# StartupMCU.net
KiCad netlist of a schematic drawn in Altium Designer
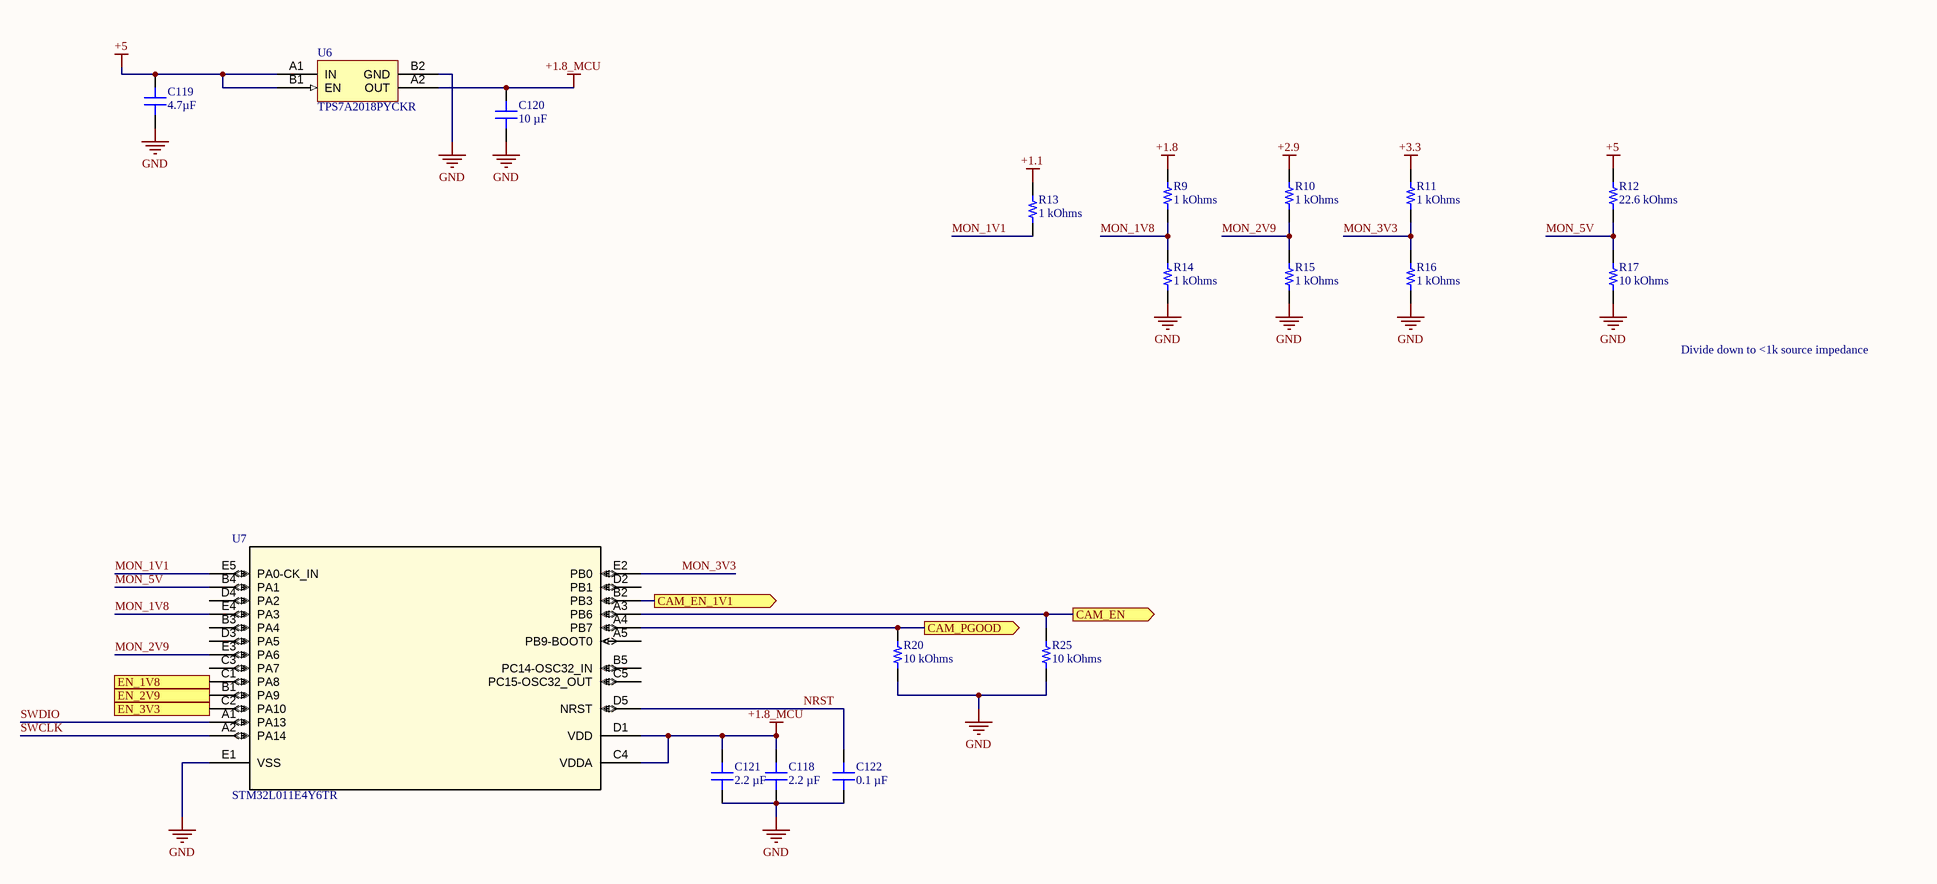
[diagram p0: StartupMCU.SchDoc]

(export (version "E")
  (design (tool "Eeschema 10.0.6"))
  (components
    (comp (ref "C118")
      (value "2.2 µF")
      (footprint "FP-GRM033-0_09-MFG")
      (description "CAP CER 2.2UF 6.3V X5R 0201")
      (fields
        (field (name "PART NUMBER") "GRM033R60J225ME01D")
        (field (name "MANUFACTURER") "Murata Electronics")
      )
      (libsource (lib "Celestial Altium Library - altium_library") (part "Capacitor"))
    )
    (comp (ref "C119")
      (value "4.7µF")
      (footprint "FP-GRM155-0_15-MFG")
      (description "CAP CER 4.7UF 10V X5R 0402")
      (fields
        (field (name "PART NUMBER") "GRM155R61A475MEAAD")
        (field (name "MANUFACTURER") "Murata Electronics")
      )
      (libsource (lib "Celestial Altium Library - altium_library") (part "Capacitor"))
    )
    (comp (ref "C120")
      (value "10 µF")
      (footprint "FP-GRM155-0_15-MFG")
      (description "CAP CER 10UF 6.3V X5R 0402")
      (fields
        (field (name "PART NUMBER") "GRM155R60J106ME15D")
        (field (name "MANUFACTURER") "Murata Electronics")
      )
      (libsource (lib "Celestial Altium Library - altium_library") (part "Capacitor"))
    )
    (comp (ref "C121")
      (value "2.2 µF")
      (footprint "FP-GRM033-0_09-MFG")
      (description "CAP CER 2.2UF 6.3V X5R 0201")
      (fields
        (field (name "PART NUMBER") "GRM033R60J225ME01D")
        (field (name "MANUFACTURER") "Murata Electronics")
      )
      (libsource (lib "Celestial Altium Library - altium_library") (part "Capacitor"))
    )
    (comp (ref "C122")
      (value "0.1 µF")
      (footprint "FP-GRM033-0_09-MFG")
      (description "CAP CER 0.1UF 16V X5R 0201")
      (fields
        (field (name "PART NUMBER") "GRM033R61C104KE14D")
        (field (name "MANUFACTURER") "Murata Electronics")
      )
      (libsource (lib "Celestial Altium Library - altium_library") (part "Capacitor"))
    )
    (comp (ref "R9")
      (value "1 kOhms")
      (footprint "RES 0201_0603")
      (description "RES SMD 1K OHM 1% 1/20W 0201")
      (fields (field (name "PART NUMBER") "CRCW02011K00FKED") (field (name "MANUFACTURER") "Vishay Dale"))
      (libsource (lib "Celestial Altium Library - altium_library") (part "Resistor"))
    )
    (comp (ref "R10")
      (value "1 kOhms")
      (footprint "RES 0201_0603")
      (description "RES SMD 1K OHM 1% 1/20W 0201")
      (fields (field (name "PART NUMBER") "CRCW02011K00FKED") (field (name "MANUFACTURER") "Vishay Dale"))
      (libsource (lib "Celestial Altium Library - altium_library") (part "Resistor"))
    )
    (comp (ref "R11")
      (value "1 kOhms")
      (footprint "RES 0201_0603")
      (description "RES SMD 1K OHM 1% 1/20W 0201")
      (fields (field (name "PART NUMBER") "CRCW02011K00FKED") (field (name "MANUFACTURER") "Vishay Dale"))
      (libsource (lib "Celestial Altium Library - altium_library") (part "Resistor"))
    )
    (comp (ref "R12")
      (value "22.6 kOhms")
      (footprint "RES 0201_0603")
      (description "RES 22.6K OHM 1% 1/20W 0201")
      (fields (field (name "PART NUMBER") "RC0201FR-0722K6L") (field (name "MANUFACTURER") "Yageo"))
      (libsource (lib "Celestial Altium Library - altium_library") (part "Resistor"))
    )
    (comp (ref "R13")
      (value "1 kOhms")
      (footprint "RES 0201_0603")
      (description "RES SMD 1K OHM 1% 1/20W 0201")
      (fields (field (name "PART NUMBER") "CRCW02011K00FKED") (field (name "MANUFACTURER") "Vishay Dale"))
      (libsource (lib "Celestial Altium Library - altium_library") (part "Resistor"))
    )
    (comp (ref "R14")
      (value "1 kOhms")
      (footprint "RES 0201_0603")
      (description "RES SMD 1K OHM 1% 1/20W 0201")
      (fields (field (name "PART NUMBER") "CRCW02011K00FKED") (field (name "MANUFACTURER") "Vishay Dale"))
      (libsource (lib "Celestial Altium Library - altium_library") (part "Resistor"))
    )
    (comp (ref "R15")
      (value "1 kOhms")
      (footprint "RES 0201_0603")
      (description "RES SMD 1K OHM 1% 1/20W 0201")
      (fields (field (name "PART NUMBER") "CRCW02011K00FKED") (field (name "MANUFACTURER") "Vishay Dale"))
      (libsource (lib "Celestial Altium Library - altium_library") (part "Resistor"))
    )
    (comp (ref "R16")
      (value "1 kOhms")
      (footprint "RES 0201_0603")
      (description "RES SMD 1K OHM 1% 1/20W 0201")
      (fields (field (name "PART NUMBER") "CRCW02011K00FKED") (field (name "MANUFACTURER") "Vishay Dale"))
      (libsource (lib "Celestial Altium Library - altium_library") (part "Resistor"))
    )
    (comp (ref "R17")
      (value "10 kOhms")
      (footprint "RES 0201_0603")
      (description "RES 10K OHM 5% 1/20W 0201")
      (fields
        (field (name "PART NUMBER") "RMCF0201JG10K0")
        (field (name "MANUFACTURER") "Stackpole Electronics Inc")
      )
      (libsource (lib "Celestial Altium Library - altium_library") (part "Resistor"))
    )
    (comp (ref "R20")
      (value "10 kOhms")
      (footprint "RES 0201_0603")
      (description "RES 10K OHM 5% 1/20W 0201")
      (fields
        (field (name "PART NUMBER") "RMCF0201JG10K0")
        (field (name "MANUFACTURER") "Stackpole Electronics Inc")
      )
      (libsource (lib "Celestial Altium Library - altium_library") (part "Resistor"))
    )
    (comp (ref "R25")
      (value "10 kOhms")
      (footprint "RES 0201_0603")
      (description "RES 10K OHM 5% 1/20W 0201")
      (fields
        (field (name "PART NUMBER") "RMCF0201JG10K0")
        (field (name "MANUFACTURER") "Stackpole Electronics Inc")
      )
      (libsource (lib "Celestial Altium Library - altium_library") (part "Resistor"))
    )
    (comp (ref "U6")
      (value "TPS7A2018PYCKR")
      (footprint "BGA4C35P2X2_62X62X35")
      (libsource (lib "SimulaVR") (part "TPS7A2018PYCKR-Symbol-1"))
    )
    (comp (ref "U7")
      (value "STM32L011E4Y6TR")
      (footprint "BGA25C40P5X5_207X213X58")
      (description "No Description Available")
      (fields (field (name "COPYRIGHT") "Copyright (C) 2022 Ultra Librarian. All rights reserved."))
      (libsource (lib "SimulaVR") (part "STM32L011E4Y6TR"))
    )
  )
  (nets
    (net (code "1") (name "+1.1") (class "Default")
      (node (ref "R13") (pin "2") (pinfunction "2_2") (pintype "passive"))
    )
    (net (code "2") (name "+1.8") (class "Default")
      (node (ref "R9") (pin "2") (pinfunction "2_2") (pintype "passive"))
    )
    (net (code "3") (name "+1.8_MCU") (class "Default")
      (node (ref "C118") (pin "2") (pinfunction "2_2") (pintype "passive"))
      (node (ref "C120") (pin "2") (pinfunction "2_2") (pintype "passive"))
      (node (ref "C121") (pin "2") (pinfunction "2_2") (pintype "passive"))
      (node (ref "U6") (pin "A2") (pinfunction "OUT_A2") (pintype "power_in"))
      (node (ref "U7") (pin "C4") (pinfunction "VDDA_C4") (pintype "power_in"))
      (node (ref "U7") (pin "D1") (pinfunction "VDD_D1") (pintype "power_in"))
    )
    (net (code "4") (name "+2.9") (class "Default")
      (node (ref "R10") (pin "2") (pinfunction "2_2") (pintype "passive"))
    )
    (net (code "5") (name "+3.3") (class "Default")
      (node (ref "R11") (pin "2") (pinfunction "2_2") (pintype "passive"))
    )
    (net (code "6") (name "+5") (class "Default")
      (node (ref "C119") (pin "2") (pinfunction "2_2") (pintype "passive"))
      (node (ref "R12") (pin "2") (pinfunction "2_2") (pintype "passive"))
      (node (ref "U6") (pin "A1") (pinfunction "IN_A1") (pintype "power_in"))
      (node (ref "U6") (pin "B1") (pinfunction "EN_B1") (pintype "input"))
    )
    (net (code "7") (name "/CAM_EN") (class "Default")
      (node (ref "R25") (pin "2") (pinfunction "2_2") (pintype "passive"))
      (node (ref "U7") (pin "A3") (pinfunction "PB6_A3") (pintype "bidirectional"))
    )
    (net (code "8") (name "/CAM_EN_1V1") (class "Default")
      (node (ref "U7") (pin "B2") (pinfunction "PB3_B2") (pintype "bidirectional"))
    )
    (net (code "9") (name "/CAM_PGOOD") (class "Default")
      (node (ref "R20") (pin "2") (pinfunction "2_2") (pintype "passive"))
      (node (ref "U7") (pin "A4") (pinfunction "PB7_A4") (pintype "bidirectional"))
    )
    (net (code "10") (name "/EN_1V8") (class "Default")
      (node (ref "U7") (pin "C1") (pinfunction "PA8_C1") (pintype "bidirectional"))
    )
    (net (code "11") (name "/EN_2V9") (class "Default")
      (node (ref "U7") (pin "B1") (pinfunction "PA9_B1") (pintype "bidirectional"))
    )
    (net (code "12") (name "/EN_3V3") (class "Default")
      (node (ref "U7") (pin "C2") (pinfunction "PA10_C2") (pintype "bidirectional"))
    )
    (net (code "13") (name "/MON_1V1") (class "Default")
      (node (ref "R13") (pin "1") (pinfunction "1_1") (pintype "passive"))
      (node (ref "U7") (pin "E5") (pinfunction "PA0-CK_IN_E5") (pintype "bidirectional"))
    )
    (net (code "14") (name "/MON_1V8") (class "Default")
      (node (ref "R14") (pin "2") (pinfunction "2_2") (pintype "passive"))
      (node (ref "R9") (pin "1") (pinfunction "1_1") (pintype "passive"))
      (node (ref "U7") (pin "E4") (pinfunction "PA3_E4") (pintype "bidirectional"))
    )
    (net (code "15") (name "/MON_2V9") (class "Default")
      (node (ref "R10") (pin "1") (pinfunction "1_1") (pintype "passive"))
      (node (ref "R15") (pin "2") (pinfunction "2_2") (pintype "passive"))
      (node (ref "U7") (pin "E3") (pinfunction "PA6_E3") (pintype "bidirectional"))
    )
    (net (code "16") (name "/MON_3V3") (class "Default")
      (node (ref "R11") (pin "1") (pinfunction "1_1") (pintype "passive"))
      (node (ref "R16") (pin "2") (pinfunction "2_2") (pintype "passive"))
      (node (ref "U7") (pin "E2") (pinfunction "PB0_E2") (pintype "bidirectional"))
    )
    (net (code "17") (name "/MON_5V") (class "Default")
      (node (ref "R12") (pin "1") (pinfunction "1_1") (pintype "passive"))
      (node (ref "R17") (pin "2") (pinfunction "2_2") (pintype "passive"))
      (node (ref "U7") (pin "B4") (pinfunction "PA1_B4") (pintype "bidirectional"))
    )
    (net (code "18") (name "/NRST") (class "Default")
      (node (ref "C122") (pin "2") (pinfunction "2_2") (pintype "passive"))
      (node (ref "U7") (pin "D5") (pinfunction "NRST_D5") (pintype "bidirectional"))
    )
    (net (code "19") (name "/SWCLK") (class "Default")
      (node (ref "U7") (pin "A2") (pinfunction "PA14_A2") (pintype "bidirectional"))
    )
    (net (code "20") (name "/SWDIO") (class "Default")
      (node (ref "U7") (pin "A1") (pinfunction "PA13_A1") (pintype "bidirectional"))
    )
    (net (code "21") (name "GND") (class "Default")
      (node (ref "C118") (pin "1") (pinfunction "1_1") (pintype "passive"))
      (node (ref "C119") (pin "1") (pinfunction "1_1") (pintype "passive"))
      (node (ref "C120") (pin "1") (pinfunction "1_1") (pintype "passive"))
      (node (ref "C121") (pin "1") (pinfunction "1_1") (pintype "passive"))
      (node (ref "C122") (pin "1") (pinfunction "1_1") (pintype "passive"))
      (node (ref "R14") (pin "1") (pinfunction "1_1") (pintype "passive"))
      (node (ref "R15") (pin "1") (pinfunction "1_1") (pintype "passive"))
      (node (ref "R16") (pin "1") (pinfunction "1_1") (pintype "passive"))
      (node (ref "R17") (pin "1") (pinfunction "1_1") (pintype "passive"))
      (node (ref "R20") (pin "1") (pinfunction "1_1") (pintype "passive"))
      (node (ref "R25") (pin "1") (pinfunction "1_1") (pintype "passive"))
      (node (ref "U6") (pin "B2") (pinfunction "GND_B2") (pintype "power_in"))
      (node (ref "U7") (pin "E1") (pinfunction "VSS_E1") (pintype "power_in"))
    )
    (net (code "22") (name "unconnected-(U7-PA2-PadD4)") (class "Default")
      (node (ref "U7") (pin "D4") (pinfunction "PA2_D4") (pintype "bidirectional"))
    )
    (net (code "23") (name "unconnected-(U7-PA4-PadB3)") (class "Default")
      (node (ref "U7") (pin "B3") (pinfunction "PA4_B3") (pintype "bidirectional"))
    )
    (net (code "24") (name "unconnected-(U7-PA5-PadD3)") (class "Default")
      (node (ref "U7") (pin "D3") (pinfunction "PA5_D3") (pintype "bidirectional"))
    )
    (net (code "25") (name "unconnected-(U7-PA7-PadC3)") (class "Default")
      (node (ref "U7") (pin "C3") (pinfunction "PA7_C3") (pintype "bidirectional"))
    )
    (net (code "26") (name "unconnected-(U7-PB1-PadD2)") (class "Default")
      (node (ref "U7") (pin "D2") (pinfunction "PB1_D2") (pintype "bidirectional"))
    )
    (net (code "27") (name "unconnected-(U7-PB9-BOOT0-PadA5)") (class "Default")
      (node (ref "U7") (pin "A5") (pinfunction "PB9-BOOT0_A5") (pintype "input"))
    )
    (net (code "28") (name "unconnected-(U7-PC14-OSC32_IN-PadB5)") (class "Default")
      (node (ref "U7") (pin "B5") (pinfunction "PC14-OSC32_IN_B5") (pintype "bidirectional"))
    )
    (net (code "29") (name "unconnected-(U7-PC15-OSC32_OUT-PadC5)") (class "Default")
      (node (ref "U7") (pin "C5") (pinfunction "PC15-OSC32_OUT_C5") (pintype "bidirectional"))
    )
  )
)
